# cerberus.net
KiCad netlist of a schematic drawn in EAGLE
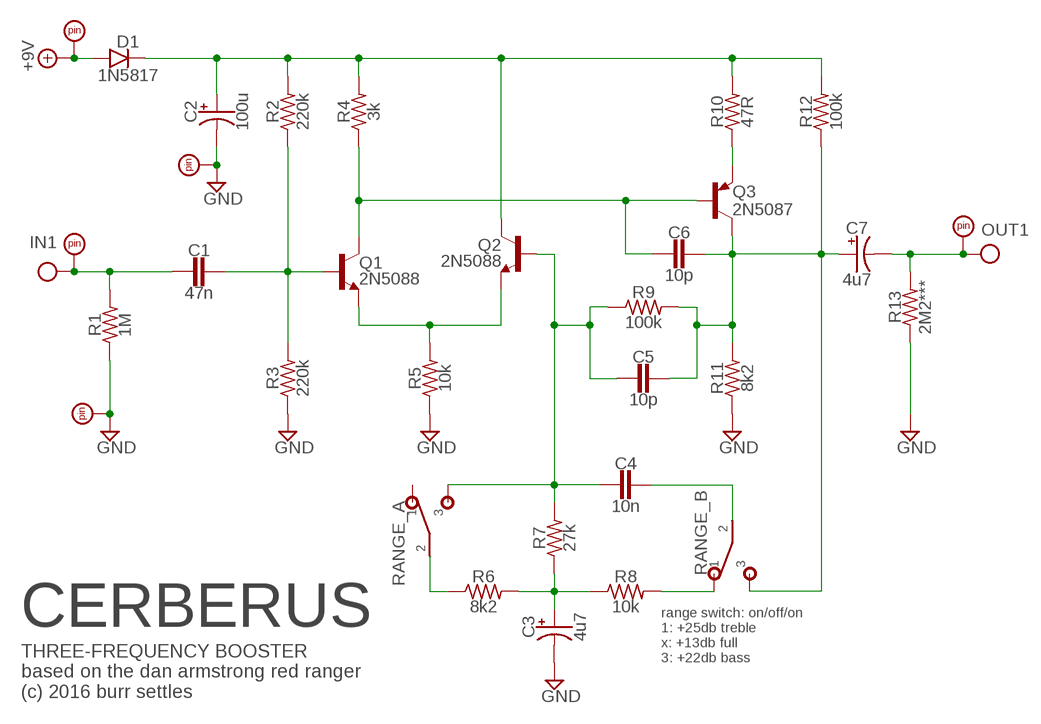
[diagram p0: schematic, sheet 1]

(export (version "E")
  (design (tool "Eeschema 10.0.6"))
  (components
    (comp (ref "C1")
      (value "47n")
      (footprint "eagle-import:BOX_SMALL")
      (libsource (lib "eagle-import") (part "CER/FILMBOX.1"))
    )
    (comp (ref "C2")
      (value "100u")
      (footprint "eagle-import:050_020_1")
      (libsource (lib "eagle-import") (part "0501"))
    )
    (comp (ref "C3")
      (value "4u7")
      (footprint "eagle-import:050_020_1")
      (libsource (lib "eagle-import") (part "0501"))
    )
    (comp (ref "C4")
      (value "10n")
      (footprint "eagle-import:BOX_SMALL")
      (libsource (lib "eagle-import") (part "CER/FILMBOX.1"))
    )
    (comp (ref "C5")
      (value "10p")
      (footprint "eagle-import:050X030_025_2")
      (libsource (lib "eagle-import") (part "CER/FILM2"))
    )
    (comp (ref "C6")
      (value "10p")
      (footprint "eagle-import:050X030_025_2")
      (libsource (lib "eagle-import") (part "CER/FILM2"))
    )
    (comp (ref "C7")
      (value "4u7")
      (footprint "eagle-import:050_020_1")
      (libsource (lib "eagle-import") (part "0501"))
    )
    (comp (ref "D1")
      (value "1N5817")
      (footprint "eagle-import:DO41-2")
      (libsource (lib "eagle-import") (part "DO41.2"))
    )
    (comp (ref "PAD1")
      (value "PADSQR")
      (footprint "eagle-import:SQUARE")
      (libsource (lib "eagle-import") (part "PADSQR"))
    )
    (comp (ref "PAD2")
      (value "PADSQR")
      (footprint "eagle-import:SQUARE")
      (libsource (lib "eagle-import") (part "PADSQR"))
    )
    (comp (ref "PAD3")
      (value "PADRND")
      (footprint "eagle-import:ROUND")
      (libsource (lib "eagle-import") (part "PADRND"))
    )
    (comp (ref "PAD4")
      (value "PADRND")
      (footprint "eagle-import:ROUND")
      (libsource (lib "eagle-import") (part "PADRND"))
    )
    (comp (ref "PAD5")
      (value "PADSQR")
      (footprint "eagle-import:SQUARE")
      (libsource (lib "eagle-import") (part "PADSQR"))
    )
    (comp (ref "Q1")
      (value "2N5088")
      (footprint "eagle-import:TO92-")
      (libsource (lib "eagle-import") (part "2N5088"))
    )
    (comp (ref "Q2")
      (value "2N5088")
      (footprint "eagle-import:TO92-")
      (libsource (lib "eagle-import") (part "2N5088"))
    )
    (comp (ref "Q3")
      (value "2N5087")
      (footprint "eagle-import:TO92-")
      (libsource (lib "eagle-import") (part "2N5087.1"))
    )
    (comp (ref "R1")
      (value "1M")
      (footprint "eagle-import:R0207_3")
      (libsource (lib "eagle-import") (part "R_.3B"))
    )
    (comp (ref "R2")
      (value "220k")
      (footprint "eagle-import:R0207_3")
      (libsource (lib "eagle-import") (part "R_.3B"))
    )
    (comp (ref "R3")
      (value "220k")
      (footprint "eagle-import:R0207_3")
      (libsource (lib "eagle-import") (part "R_.3B"))
    )
    (comp (ref "R4")
      (value "3k")
      (footprint "eagle-import:R0207_3")
      (libsource (lib "eagle-import") (part "R_.3B"))
    )
    (comp (ref "R5")
      (value "10k")
      (footprint "eagle-import:R0207_3")
      (libsource (lib "eagle-import") (part "R_.3B"))
    )
    (comp (ref "R6")
      (value "8k2")
      (footprint "eagle-import:R0207_3")
      (libsource (lib "eagle-import") (part "R_.3B"))
    )
    (comp (ref "R7")
      (value "27k")
      (footprint "eagle-import:R0207_3")
      (libsource (lib "eagle-import") (part "R_.3B"))
    )
    (comp (ref "R8")
      (value "10k")
      (footprint "eagle-import:R0207_3")
      (libsource (lib "eagle-import") (part "R_.3B"))
    )
    (comp (ref "R9")
      (value "100k")
      (footprint "eagle-import:R0207_3")
      (libsource (lib "eagle-import") (part "R_.3B"))
    )
    (comp (ref "R10")
      (value "47R")
      (footprint "eagle-import:R0207_3")
      (libsource (lib "eagle-import") (part "R_.3B"))
    )
    (comp (ref "R11")
      (value "8k2")
      (footprint "eagle-import:R0207_3")
      (libsource (lib "eagle-import") (part "R_.3B"))
    )
    (comp (ref "R12")
      (value "100k")
      (footprint "eagle-import:R0207_3")
      (libsource (lib "eagle-import") (part "R_.3B"))
    )
    (comp (ref "R13")
      (value "2M2***")
      (footprint "eagle-import:R0207_3")
      (libsource (lib "eagle-import") (part "R_.3B"))
    )
    (comp (ref "RANGE")
      (value "DPDT")
      (footprint "eagle-import:DPDT_PADS")
      (libsource (lib "eagle-import") (part "DPDTPADS"))
    )
  )
  (nets
    (net (code "1") (name "+9V") (class "Default")
      (node (ref "D1") (pin "A") (pinfunction "A_A") (pintype "passive"))
      (node (ref "PAD1") (pin "1") (pinfunction "P$1_1") (pintype "bidirectional"))
    )
    (net (code "2") (name "GND") (class "Default")
      (node (ref "C2") (pin "-") (pinfunction "-_-") (pintype "passive"))
      (node (ref "C3") (pin "-") (pinfunction "-_-") (pintype "passive"))
      (node (ref "PAD3") (pin "1") (pinfunction "P$1_1") (pintype "bidirectional"))
      (node (ref "PAD4") (pin "1") (pinfunction "P$1_1") (pintype "bidirectional"))
      (node (ref "R1") (pin "1") (pinfunction "1_1") (pintype "passive"))
      (node (ref "R11") (pin "1") (pinfunction "1_1") (pintype "passive"))
      (node (ref "R13") (pin "1") (pinfunction "1_1") (pintype "passive"))
      (node (ref "R3") (pin "1") (pinfunction "1_1") (pintype "passive"))
      (node (ref "R5") (pin "1") (pinfunction "1_1") (pintype "passive"))
    )
    (net (code "3") (name "IN") (class "Default")
      (node (ref "C1") (pin "2") (pinfunction "2_2") (pintype "passive"))
      (node (ref "PAD2") (pin "1") (pinfunction "P$1_1") (pintype "bidirectional"))
      (node (ref "R1") (pin "2") (pinfunction "2_2") (pintype "passive"))
    )
    (net (code "4") (name "Net-(C3-Pad+)") (class "Default")
      (node (ref "C3") (pin "+") (pinfunction "+_+") (pintype "passive"))
      (node (ref "R6") (pin "2") (pinfunction "2_2") (pintype "passive"))
      (node (ref "R7") (pin "1") (pinfunction "1_1") (pintype "passive"))
      (node (ref "R8") (pin "1") (pinfunction "1_1") (pintype "passive"))
    )
    (net (code "5") (name "Net-(Q1-B)") (class "Default")
      (node (ref "C1") (pin "1") (pinfunction "1_1") (pintype "passive"))
      (node (ref "Q1") (pin "2") (pinfunction "B_2") (pintype "passive"))
      (node (ref "R2") (pin "1") (pinfunction "1_1") (pintype "passive"))
      (node (ref "R3") (pin "2") (pinfunction "2_2") (pintype "passive"))
    )
    (net (code "6") (name "Net-(Q1-C)") (class "Default")
      (node (ref "C6") (pin "2") (pinfunction "2_2") (pintype "passive"))
      (node (ref "Q1") (pin "1") (pinfunction "C_1") (pintype "passive"))
      (node (ref "Q3") (pin "2") (pinfunction "B_2") (pintype "passive"))
      (node (ref "R4") (pin "1") (pinfunction "1_1") (pintype "passive"))
    )
    (net (code "7") (name "Net-(Q1-E)") (class "Default")
      (node (ref "Q1") (pin "3") (pinfunction "E_3") (pintype "passive"))
      (node (ref "Q2") (pin "3") (pinfunction "E_3") (pintype "passive"))
      (node (ref "R5") (pin "2") (pinfunction "2_2") (pintype "passive"))
    )
    (net (code "8") (name "Net-(Q2-B)") (class "Default")
      (node (ref "C4") (pin "2") (pinfunction "2_2") (pintype "passive"))
      (node (ref "C5") (pin "2") (pinfunction "2_2") (pintype "passive"))
      (node (ref "Q2") (pin "2") (pinfunction "B_2") (pintype "passive"))
      (node (ref "R7") (pin "2") (pinfunction "2_2") (pintype "passive"))
      (node (ref "R9") (pin "1") (pinfunction "1_1") (pintype "passive"))
      (node (ref "RANGE") (pin "P$3") (pinfunction "3_P$3") (pintype "passive"))
    )
    (net (code "9") (name "Net-(Q2-C)") (class "Default")
      (node (ref "C2") (pin "+") (pinfunction "+_+") (pintype "passive"))
      (node (ref "D1") (pin "C") (pinfunction "C_C") (pintype "passive"))
      (node (ref "Q2") (pin "1") (pinfunction "C_1") (pintype "passive"))
      (node (ref "R10") (pin "2") (pinfunction "2_2") (pintype "passive"))
      (node (ref "R12") (pin "2") (pinfunction "2_2") (pintype "passive"))
      (node (ref "R2") (pin "2") (pinfunction "2_2") (pintype "passive"))
      (node (ref "R4") (pin "2") (pinfunction "2_2") (pintype "passive"))
    )
    (net (code "10") (name "Net-(Q3-C)") (class "Default")
      (node (ref "C5") (pin "1") (pinfunction "1_1") (pintype "passive"))
      (node (ref "C6") (pin "1") (pinfunction "1_1") (pintype "passive"))
      (node (ref "C7") (pin "+") (pinfunction "+_+") (pintype "passive"))
      (node (ref "Q3") (pin "1") (pinfunction "C_1") (pintype "passive"))
      (node (ref "R11") (pin "2") (pinfunction "2_2") (pintype "passive"))
      (node (ref "R12") (pin "1") (pinfunction "1_1") (pintype "passive"))
      (node (ref "R9") (pin "2") (pinfunction "2_2") (pintype "passive"))
      (node (ref "RANGE") (pin "P$6") (pinfunction "3_P$6") (pintype "passive"))
    )
    (net (code "11") (name "Net-(Q3-E)") (class "Default")
      (node (ref "Q3") (pin "3") (pinfunction "E_3") (pintype "passive"))
      (node (ref "R10") (pin "1") (pinfunction "1_1") (pintype "passive"))
    )
    (net (code "12") (name "Net-(RANGEA-2)") (class "Default")
      (node (ref "R6") (pin "1") (pinfunction "1_1") (pintype "passive"))
      (node (ref "RANGE") (pin "P$2") (pinfunction "2_P$2") (pintype "passive"))
    )
    (net (code "13") (name "Net-(RANGEB-1)") (class "Default")
      (node (ref "R8") (pin "2") (pinfunction "2_2") (pintype "passive"))
      (node (ref "RANGE") (pin "P$4") (pinfunction "1_P$4") (pintype "passive"))
    )
    (net (code "14") (name "Net-(RANGEB-2)") (class "Default")
      (node (ref "C4") (pin "1") (pinfunction "1_1") (pintype "passive"))
      (node (ref "RANGE") (pin "P$5") (pinfunction "2_P$5") (pintype "passive"))
    )
    (net (code "15") (name "OUT") (class "Default")
      (node (ref "C7") (pin "-") (pinfunction "-_-") (pintype "passive"))
      (node (ref "PAD5") (pin "1") (pinfunction "P$1_1") (pintype "bidirectional"))
      (node (ref "R13") (pin "2") (pinfunction "2_2") (pintype "passive"))
    )
    (net (code "16") (name "unconnected-(RANGEA-1-PadP$1)") (class "Default")
      (node (ref "RANGE") (pin "P$1") (pinfunction "1_P$1") (pintype "passive"))
    )
  )
)
